# ezo_single_smaller.net
KiCad netlist of a schematic drawn in EAGLE
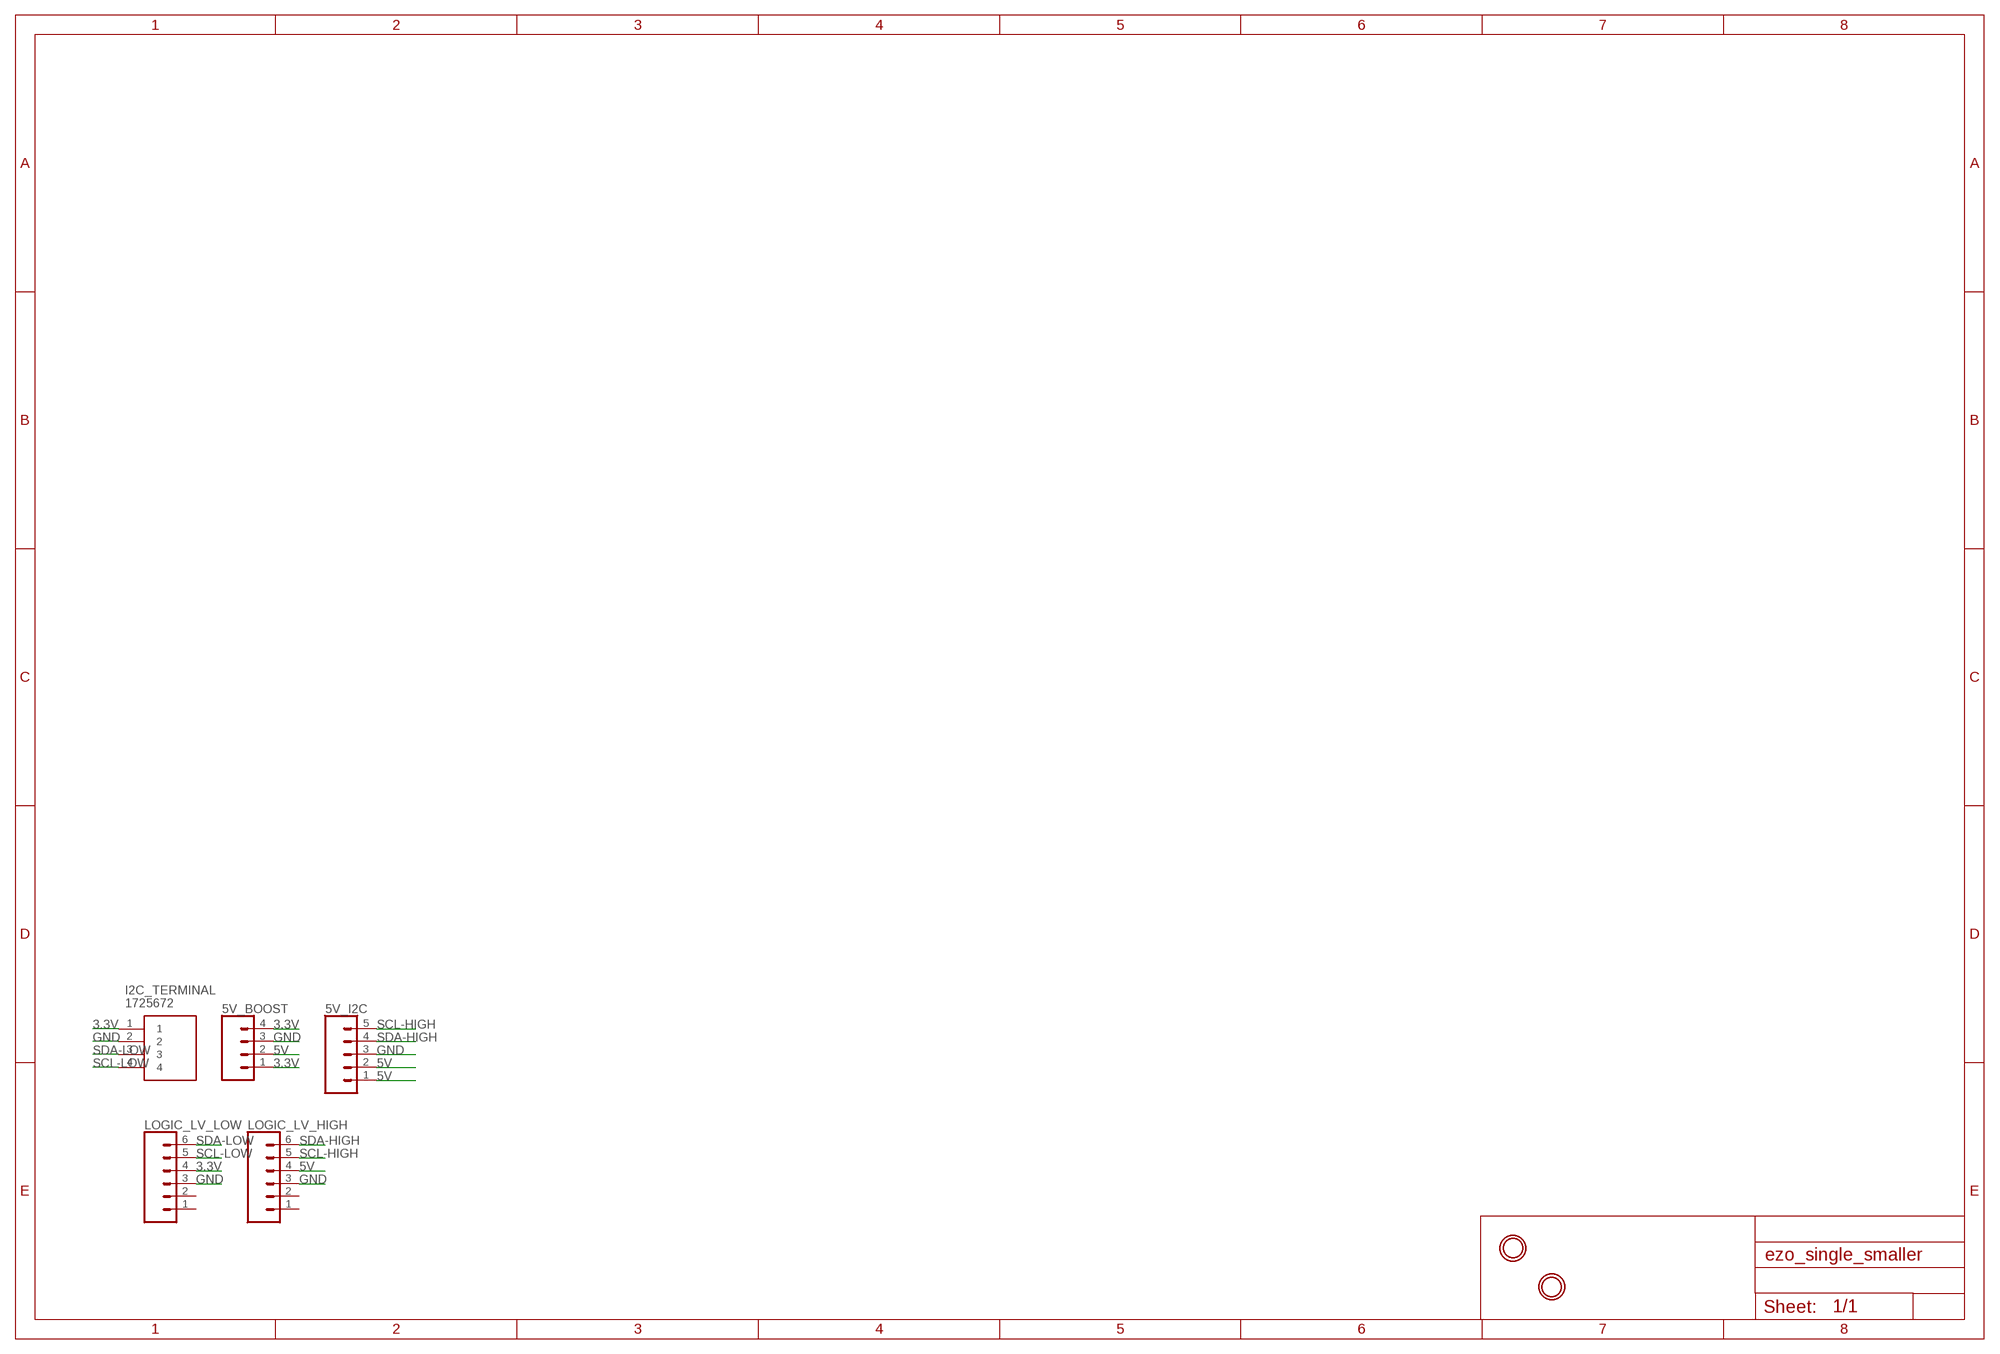
[diagram p0: schematic, sheet 1]

(export (version "E")
  (design (tool "Eeschema 10.0.6"))
  (components
    (comp (ref "5V_BOOST")
      (value "CONN_04PTH")
      (footprint "eagle-import:1X04")
      (libsource (lib "eagle-import") (part "CONN_04PTH"))
    )
    (comp (ref "5V_I2C")
      (value "CONN_05PTH")
      (footprint "eagle-import:1X05")
      (libsource (lib "eagle-import") (part "CONN_05PTH"))
    )
    (comp (ref "I2C_TERMINAL")
      (value "1725672")
      (footprint "eagle-import:1725672")
      (fields (field (name "MOUSER_PART_NUMBER") "651-1725672"))
      (libsource (lib "eagle-import") (part "1725672"))
    )
    (comp (ref "LOGIC_LV_HIGH")
      (value "CONN_06SILK_FEMALE_PTH")
      (footprint "eagle-import:1X06")
      (libsource (lib "eagle-import") (part "CONN_06SILK_FEMALE_PTH"))
    )
    (comp (ref "LOGIC_LV_LOW")
      (value "CONN_06SILK_FEMALE_PTH")
      (footprint "eagle-import:1X06")
      (libsource (lib "eagle-import") (part "CONN_06SILK_FEMALE_PTH"))
    )
    (comp (ref "U$1")
      (value "MOUNTINGHOLE2.5")
      (footprint "eagle-import:MOUNTINGHOLE_2.5_PLATED")
      (libsource (lib "eagle-import") (part "MOUNTINGHOLE2.5"))
    )
    (comp (ref "U$3")
      (value "MOUNTINGHOLE2.5")
      (footprint "eagle-import:MOUNTINGHOLE_2.5_PLATED")
      (libsource (lib "eagle-import") (part "MOUNTINGHOLE2.5"))
    )
  )
  (nets
    (net (code "1") (name "/3.3V") (class "Default")
      (node (ref "5V_BOOST") (pin "1") (pinfunction "1_1") (pintype "passive"))
      (node (ref "5V_BOOST") (pin "4") (pinfunction "4_4") (pintype "passive"))
      (node (ref "I2C_TERMINAL") (pin "1") (pinfunction "1_1") (pintype "bidirectional"))
      (node (ref "LOGIC_LV_LOW") (pin "4") (pinfunction "4_4") (pintype "passive"))
    )
    (net (code "2") (name "/5V") (class "Default")
      (node (ref "5V_BOOST") (pin "2") (pinfunction "2_2") (pintype "passive"))
      (node (ref "5V_I2C") (pin "1") (pinfunction "1_1") (pintype "passive"))
      (node (ref "5V_I2C") (pin "2") (pinfunction "2_2") (pintype "passive"))
      (node (ref "LOGIC_LV_HIGH") (pin "4") (pinfunction "4_4") (pintype "passive"))
    )
    (net (code "3") (name "/GND") (class "Default")
      (node (ref "5V_BOOST") (pin "3") (pinfunction "3_3") (pintype "passive"))
      (node (ref "5V_I2C") (pin "3") (pinfunction "3_3") (pintype "passive"))
      (node (ref "I2C_TERMINAL") (pin "2") (pinfunction "2_2") (pintype "bidirectional"))
      (node (ref "LOGIC_LV_HIGH") (pin "3") (pinfunction "3_3") (pintype "passive"))
      (node (ref "LOGIC_LV_LOW") (pin "3") (pinfunction "3_3") (pintype "passive"))
    )
    (net (code "4") (name "/SCL-HIGH") (class "Default")
      (node (ref "5V_I2C") (pin "5") (pinfunction "5_5") (pintype "passive"))
      (node (ref "LOGIC_LV_HIGH") (pin "5") (pinfunction "5_5") (pintype "passive"))
    )
    (net (code "5") (name "/SCL-LOW") (class "Default")
      (node (ref "I2C_TERMINAL") (pin "4") (pinfunction "4_4") (pintype "bidirectional"))
      (node (ref "LOGIC_LV_LOW") (pin "5") (pinfunction "5_5") (pintype "passive"))
    )
    (net (code "6") (name "/SDA-HIGH") (class "Default")
      (node (ref "5V_I2C") (pin "4") (pinfunction "4_4") (pintype "passive"))
      (node (ref "LOGIC_LV_HIGH") (pin "6") (pinfunction "6_6") (pintype "passive"))
    )
    (net (code "7") (name "/SDA-LOW") (class "Default")
      (node (ref "I2C_TERMINAL") (pin "3") (pinfunction "3_3") (pintype "bidirectional"))
      (node (ref "LOGIC_LV_LOW") (pin "6") (pinfunction "6_6") (pintype "passive"))
    )
    (net (code "8") (name "unconnected-(LOGIC_LV_HIGH-Pad1)") (class "Default")
      (node (ref "LOGIC_LV_HIGH") (pin "1") (pinfunction "1_1") (pintype "passive"))
    )
    (net (code "9") (name "unconnected-(LOGIC_LV_HIGH-Pad2)") (class "Default")
      (node (ref "LOGIC_LV_HIGH") (pin "2") (pinfunction "2_2") (pintype "passive"))
    )
    (net (code "10") (name "unconnected-(LOGIC_LV_LOW-Pad1)") (class "Default")
      (node (ref "LOGIC_LV_LOW") (pin "1") (pinfunction "1_1") (pintype "passive"))
    )
    (net (code "11") (name "unconnected-(LOGIC_LV_LOW-Pad2)") (class "Default")
      (node (ref "LOGIC_LV_LOW") (pin "2") (pinfunction "2_2") (pintype "passive"))
    )
  )
)
